# proto_Feather_with_Weather_0v20.net
KiCad netlist of a schematic drawn in EAGLE
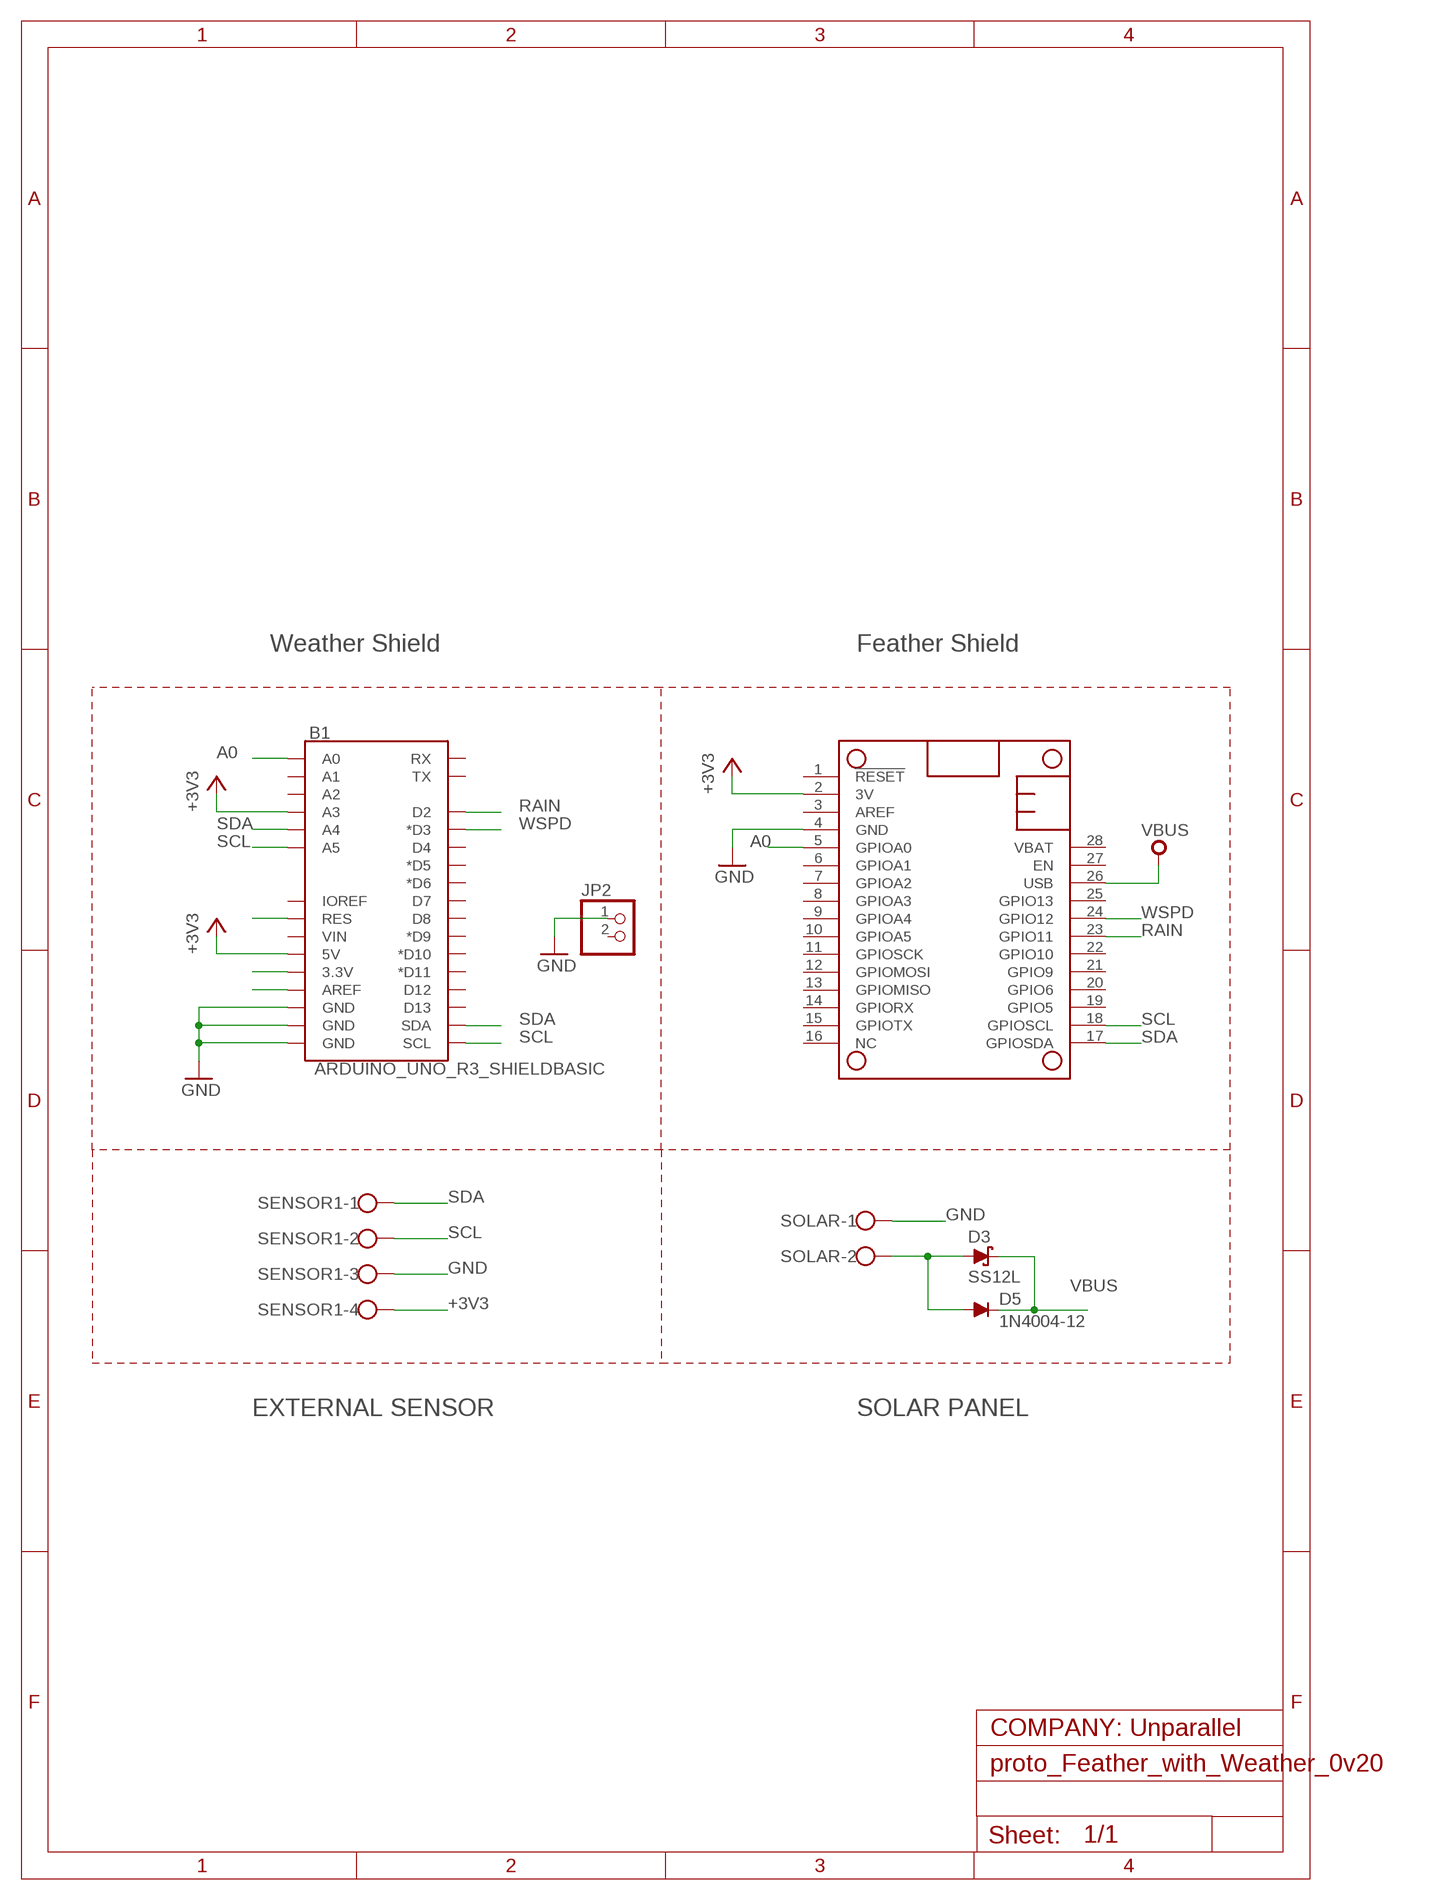
[diagram p0: schematic, sheet 1]

(export (version "E")
  (design (tool "Eeschema 10.0.6"))
  (components
    (comp (ref "B1")
      (value "ARDUINO_UNO_R3_SHIELDBASIC")
      (footprint "eagle-import:UNO_R3_SHIELD")
      (libsource (lib "eagle-import") (part "ARDUINO_UNO_R3_SHIELDBASIC"))
    )
    (comp (ref "D3")
      (value "SS12L")
      (footprint "eagle-import:SUB_SMA_PROTO")
      (libsource (lib "eagle-import") (part "SCHOTTKY-DIODESUB_SMA_PROTO"))
    )
    (comp (ref "D5")
      (value "1N4004-12")
      (footprint "eagle-import:DO41-12")
      (libsource (lib "eagle-import") (part "1N4004-12"))
    )
    (comp (ref "JP2")
      (value "PINHD-1X2")
      (footprint "eagle-import:1X02")
      (libsource (lib "eagle-import") (part "PINHD-1X2"))
    )
    (comp (ref "MS2")
      (value "FEATHERWING_NODIM")
      (footprint "eagle-import:FEATHERWING_DIM")
      (libsource (lib "eagle-import") (part "FEATHERWING_NODIM"))
    )
    (comp (ref "SENSOR1")
      (value "W237-4")
      (footprint "eagle-import:W237-4")
      (libsource (lib "eagle-import") (part "W237-4"))
    )
    (comp (ref "SOLAR")
      (value "W237-102")
      (footprint "eagle-import:W237-102")
      (libsource (lib "eagle-import") (part "W237-102"))
    )
  )
  (nets
    (net (code "1") (name "+3V3") (class "Default")
      (node (ref "B1") (pin "5V") (pinfunction "5V_5V") (pintype "bidirectional"))
      (node (ref "B1") (pin "A3") (pinfunction "A3_A3") (pintype "bidirectional"))
      (node (ref "MS2") (pin "2") (pinfunction "3V_2") (pintype "power_in"))
      (node (ref "SENSOR1") (pin "4") (pinfunction "KL_4") (pintype "passive"))
    )
    (net (code "2") (name "/A0") (class "Default")
      (node (ref "B1") (pin "A0") (pinfunction "A0_A0") (pintype "bidirectional"))
      (node (ref "MS2") (pin "5") (pinfunction "GPIOA0_5") (pintype "bidirectional"))
    )
    (net (code "3") (name "/RAIN") (class "Default")
      (node (ref "B1") (pin "D2") (pinfunction "D2_D2") (pintype "bidirectional"))
      (node (ref "MS2") (pin "23") (pinfunction "GPIO11_23") (pintype "bidirectional"))
    )
    (net (code "4") (name "/SCL") (class "Default")
      (node (ref "B1") (pin "A5") (pinfunction "A5_A5") (pintype "bidirectional"))
      (node (ref "B1") (pin "SCL") (pinfunction "SCL_SCL") (pintype "bidirectional"))
      (node (ref "MS2") (pin "18") (pinfunction "GPIOSCL_18") (pintype "bidirectional"))
      (node (ref "SENSOR1") (pin "2") (pinfunction "KL_2") (pintype "passive"))
    )
    (net (code "5") (name "/SDA") (class "Default")
      (node (ref "B1") (pin "A4") (pinfunction "A4_A4") (pintype "bidirectional"))
      (node (ref "B1") (pin "SDA") (pinfunction "SDA_SDA") (pintype "bidirectional"))
      (node (ref "MS2") (pin "17") (pinfunction "GPIOSDA_17") (pintype "bidirectional"))
      (node (ref "SENSOR1") (pin "1") (pinfunction "KL_1") (pintype "passive"))
    )
    (net (code "6") (name "/VBAT") (class "Default")
      (node (ref "MS2") (pin "28") (pinfunction "VBAT_28") (pintype "power_in"))
    )
    (net (code "7") (name "/WSPD") (class "Default")
      (node (ref "B1") (pin "D3") (pinfunction "*D3_D3") (pintype "bidirectional"))
      (node (ref "MS2") (pin "24") (pinfunction "GPIO12_24") (pintype "bidirectional"))
    )
    (net (code "8") (name "GND") (class "Default")
      (node (ref "B1") (pin "GND@0") (pinfunction "GND_GND@0") (pintype "bidirectional"))
      (node (ref "B1") (pin "GND@1") (pinfunction "GND_GND@1") (pintype "bidirectional"))
      (node (ref "B1") (pin "GND@2") (pinfunction "GND_GND@2") (pintype "bidirectional"))
      (node (ref "JP2") (pin "1") (pinfunction "1_1") (pintype "passive"))
      (node (ref "MS2") (pin "4") (pinfunction "GND_4") (pintype "power_in"))
      (node (ref "SENSOR1") (pin "3") (pinfunction "KL_3") (pintype "passive"))
      (node (ref "SOLAR") (pin "1") (pinfunction "KL_1") (pintype "passive"))
    )
    (net (code "9") (name "Net-(SOLARB-KL)") (class "Default")
      (node (ref "D3") (pin "A") (pinfunction "A_A") (pintype "passive"))
      (node (ref "D5") (pin "A") (pinfunction "A_A") (pintype "passive"))
      (node (ref "SOLAR") (pin "2") (pinfunction "KL_2") (pintype "passive"))
    )
    (net (code "10") (name "VBUS") (class "Default")
      (node (ref "D3") (pin "C") (pinfunction "C_C") (pintype "passive"))
      (node (ref "D5") (pin "C") (pinfunction "C_C") (pintype "passive"))
      (node (ref "MS2") (pin "26") (pinfunction "USB_26") (pintype "power_in"))
    )
    (net (code "11") (name "unconnected-(B1-*D5-PadD5)") (class "Default")
      (node (ref "B1") (pin "D5") (pinfunction "*D5_D5") (pintype "bidirectional"))
    )
    (net (code "12") (name "unconnected-(B1-*D6-PadD6)") (class "Default")
      (node (ref "B1") (pin "D6") (pinfunction "*D6_D6") (pintype "bidirectional"))
    )
    (net (code "13") (name "unconnected-(B1-*D9-PadD9)") (class "Default")
      (node (ref "B1") (pin "D9") (pinfunction "*D9_D9") (pintype "bidirectional"))
    )
    (net (code "14") (name "unconnected-(B1-*D10-PadD10)") (class "Default")
      (node (ref "B1") (pin "D10") (pinfunction "*D10_D10") (pintype "bidirectional"))
    )
    (net (code "15") (name "unconnected-(B1-*D11-PadD11)") (class "Default")
      (node (ref "B1") (pin "D11") (pinfunction "*D11_D11") (pintype "bidirectional"))
    )
    (net (code "16") (name "unconnected-(B1-Pad3.3V)") (class "Default")
      (node (ref "B1") (pin "3.3V") (pinfunction "3.3V_3.3V") (pintype "bidirectional"))
    )
    (net (code "17") (name "unconnected-(B1-PadA1)") (class "Default")
      (node (ref "B1") (pin "A1") (pinfunction "A1_A1") (pintype "bidirectional"))
    )
    (net (code "18") (name "unconnected-(B1-PadA2)") (class "Default")
      (node (ref "B1") (pin "A2") (pinfunction "A2_A2") (pintype "bidirectional"))
    )
    (net (code "19") (name "unconnected-(B1-PadAREF)") (class "Default")
      (node (ref "B1") (pin "AREF") (pinfunction "AREF_AREF") (pintype "bidirectional"))
    )
    (net (code "20") (name "unconnected-(B1-PadD4)") (class "Default")
      (node (ref "B1") (pin "D4") (pinfunction "D4_D4") (pintype "bidirectional"))
    )
    (net (code "21") (name "unconnected-(B1-PadD7)") (class "Default")
      (node (ref "B1") (pin "D7") (pinfunction "D7_D7") (pintype "bidirectional"))
    )
    (net (code "22") (name "unconnected-(B1-PadD8)") (class "Default")
      (node (ref "B1") (pin "D8") (pinfunction "D8_D8") (pintype "bidirectional"))
    )
    (net (code "23") (name "unconnected-(B1-PadD12)") (class "Default")
      (node (ref "B1") (pin "D12") (pinfunction "D12_D12") (pintype "bidirectional"))
    )
    (net (code "24") (name "unconnected-(B1-PadD13)") (class "Default")
      (node (ref "B1") (pin "D13") (pinfunction "D13_D13") (pintype "bidirectional"))
    )
    (net (code "25") (name "unconnected-(B1-PadIOREF)") (class "Default")
      (node (ref "B1") (pin "IOREF") (pinfunction "IOREF_IOREF") (pintype "bidirectional"))
    )
    (net (code "26") (name "unconnected-(B1-PadRES)") (class "Default")
      (node (ref "B1") (pin "RES") (pinfunction "RES_RES") (pintype "bidirectional"))
    )
    (net (code "27") (name "unconnected-(B1-PadRX)") (class "Default")
      (node (ref "B1") (pin "RX") (pinfunction "RX_RX") (pintype "bidirectional"))
    )
    (net (code "28") (name "unconnected-(B1-PadTX)") (class "Default")
      (node (ref "B1") (pin "TX") (pinfunction "TX_TX") (pintype "bidirectional"))
    )
    (net (code "29") (name "unconnected-(B1-PadVIN)") (class "Default")
      (node (ref "B1") (pin "VIN") (pinfunction "VIN_VIN") (pintype "bidirectional"))
    )
    (net (code "30") (name "unconnected-(JP2-Pad2)") (class "Default")
      (node (ref "JP2") (pin "2") (pinfunction "2_2") (pintype "passive"))
    )
    (net (code "31") (name "unconnected-(MS2-AREF-Pad3)") (class "Default")
      (node (ref "MS2") (pin "3") (pinfunction "AREF_3") (pintype "passive"))
    )
    (net (code "32") (name "unconnected-(MS2-EN-Pad27)") (class "Default")
      (node (ref "MS2") (pin "27") (pinfunction "EN_27") (pintype "passive"))
    )
    (net (code "33") (name "unconnected-(MS2-GPIO5-Pad19)") (class "Default")
      (node (ref "MS2") (pin "19") (pinfunction "GPIO5_19") (pintype "bidirectional"))
    )
    (net (code "34") (name "unconnected-(MS2-GPIO6-Pad20)") (class "Default")
      (node (ref "MS2") (pin "20") (pinfunction "GPIO6_20") (pintype "bidirectional"))
    )
    (net (code "35") (name "unconnected-(MS2-GPIO9-Pad21)") (class "Default")
      (node (ref "MS2") (pin "21") (pinfunction "GPIO9_21") (pintype "bidirectional"))
    )
    (net (code "36") (name "unconnected-(MS2-GPIO10-Pad22)") (class "Default")
      (node (ref "MS2") (pin "22") (pinfunction "GPIO10_22") (pintype "bidirectional"))
    )
    (net (code "37") (name "unconnected-(MS2-GPIO13-Pad25)") (class "Default")
      (node (ref "MS2") (pin "25") (pinfunction "GPIO13_25") (pintype "bidirectional"))
    )
    (net (code "38") (name "unconnected-(MS2-GPIOA1-Pad6)") (class "Default")
      (node (ref "MS2") (pin "6") (pinfunction "GPIOA1_6") (pintype "bidirectional"))
    )
    (net (code "39") (name "unconnected-(MS2-GPIOA2-Pad7)") (class "Default")
      (node (ref "MS2") (pin "7") (pinfunction "GPIOA2_7") (pintype "bidirectional"))
    )
    (net (code "40") (name "unconnected-(MS2-GPIOA3-Pad8)") (class "Default")
      (node (ref "MS2") (pin "8") (pinfunction "GPIOA3_8") (pintype "bidirectional"))
    )
    (net (code "41") (name "unconnected-(MS2-GPIOA4-Pad9)") (class "Default")
      (node (ref "MS2") (pin "9") (pinfunction "GPIOA4_9") (pintype "bidirectional"))
    )
    (net (code "42") (name "unconnected-(MS2-GPIOA5-Pad10)") (class "Default")
      (node (ref "MS2") (pin "10") (pinfunction "GPIOA5_10") (pintype "bidirectional"))
    )
    (net (code "43") (name "unconnected-(MS2-GPIOMISO-Pad13)") (class "Default")
      (node (ref "MS2") (pin "13") (pinfunction "GPIOMISO_13") (pintype "bidirectional"))
    )
    (net (code "44") (name "unconnected-(MS2-GPIOMOSI-Pad12)") (class "Default")
      (node (ref "MS2") (pin "12") (pinfunction "GPIOMOSI_12") (pintype "bidirectional"))
    )
    (net (code "45") (name "unconnected-(MS2-GPIORX-Pad14)") (class "Default")
      (node (ref "MS2") (pin "14") (pinfunction "GPIORX_14") (pintype "bidirectional"))
    )
    (net (code "46") (name "unconnected-(MS2-GPIOSCK-Pad11)") (class "Default")
      (node (ref "MS2") (pin "11") (pinfunction "GPIOSCK_11") (pintype "bidirectional"))
    )
    (net (code "47") (name "unconnected-(MS2-GPIOTX-Pad15)") (class "Default")
      (node (ref "MS2") (pin "15") (pinfunction "GPIOTX_15") (pintype "bidirectional"))
    )
    (net (code "48") (name "unconnected-(MS2-NC-Pad16)") (class "Default")
      (node (ref "MS2") (pin "16") (pinfunction "NC_16") (pintype "passive"))
    )
    (net (code "49") (name "unconnected-(MS2-~{RESET}-Pad1)") (class "Default")
      (node (ref "MS2") (pin "1") (pinfunction "~{RESET}_1") (pintype "input"))
    )
  )
)
